# p1-001.net
KiCad netlist of a schematic drawn in EAGLE
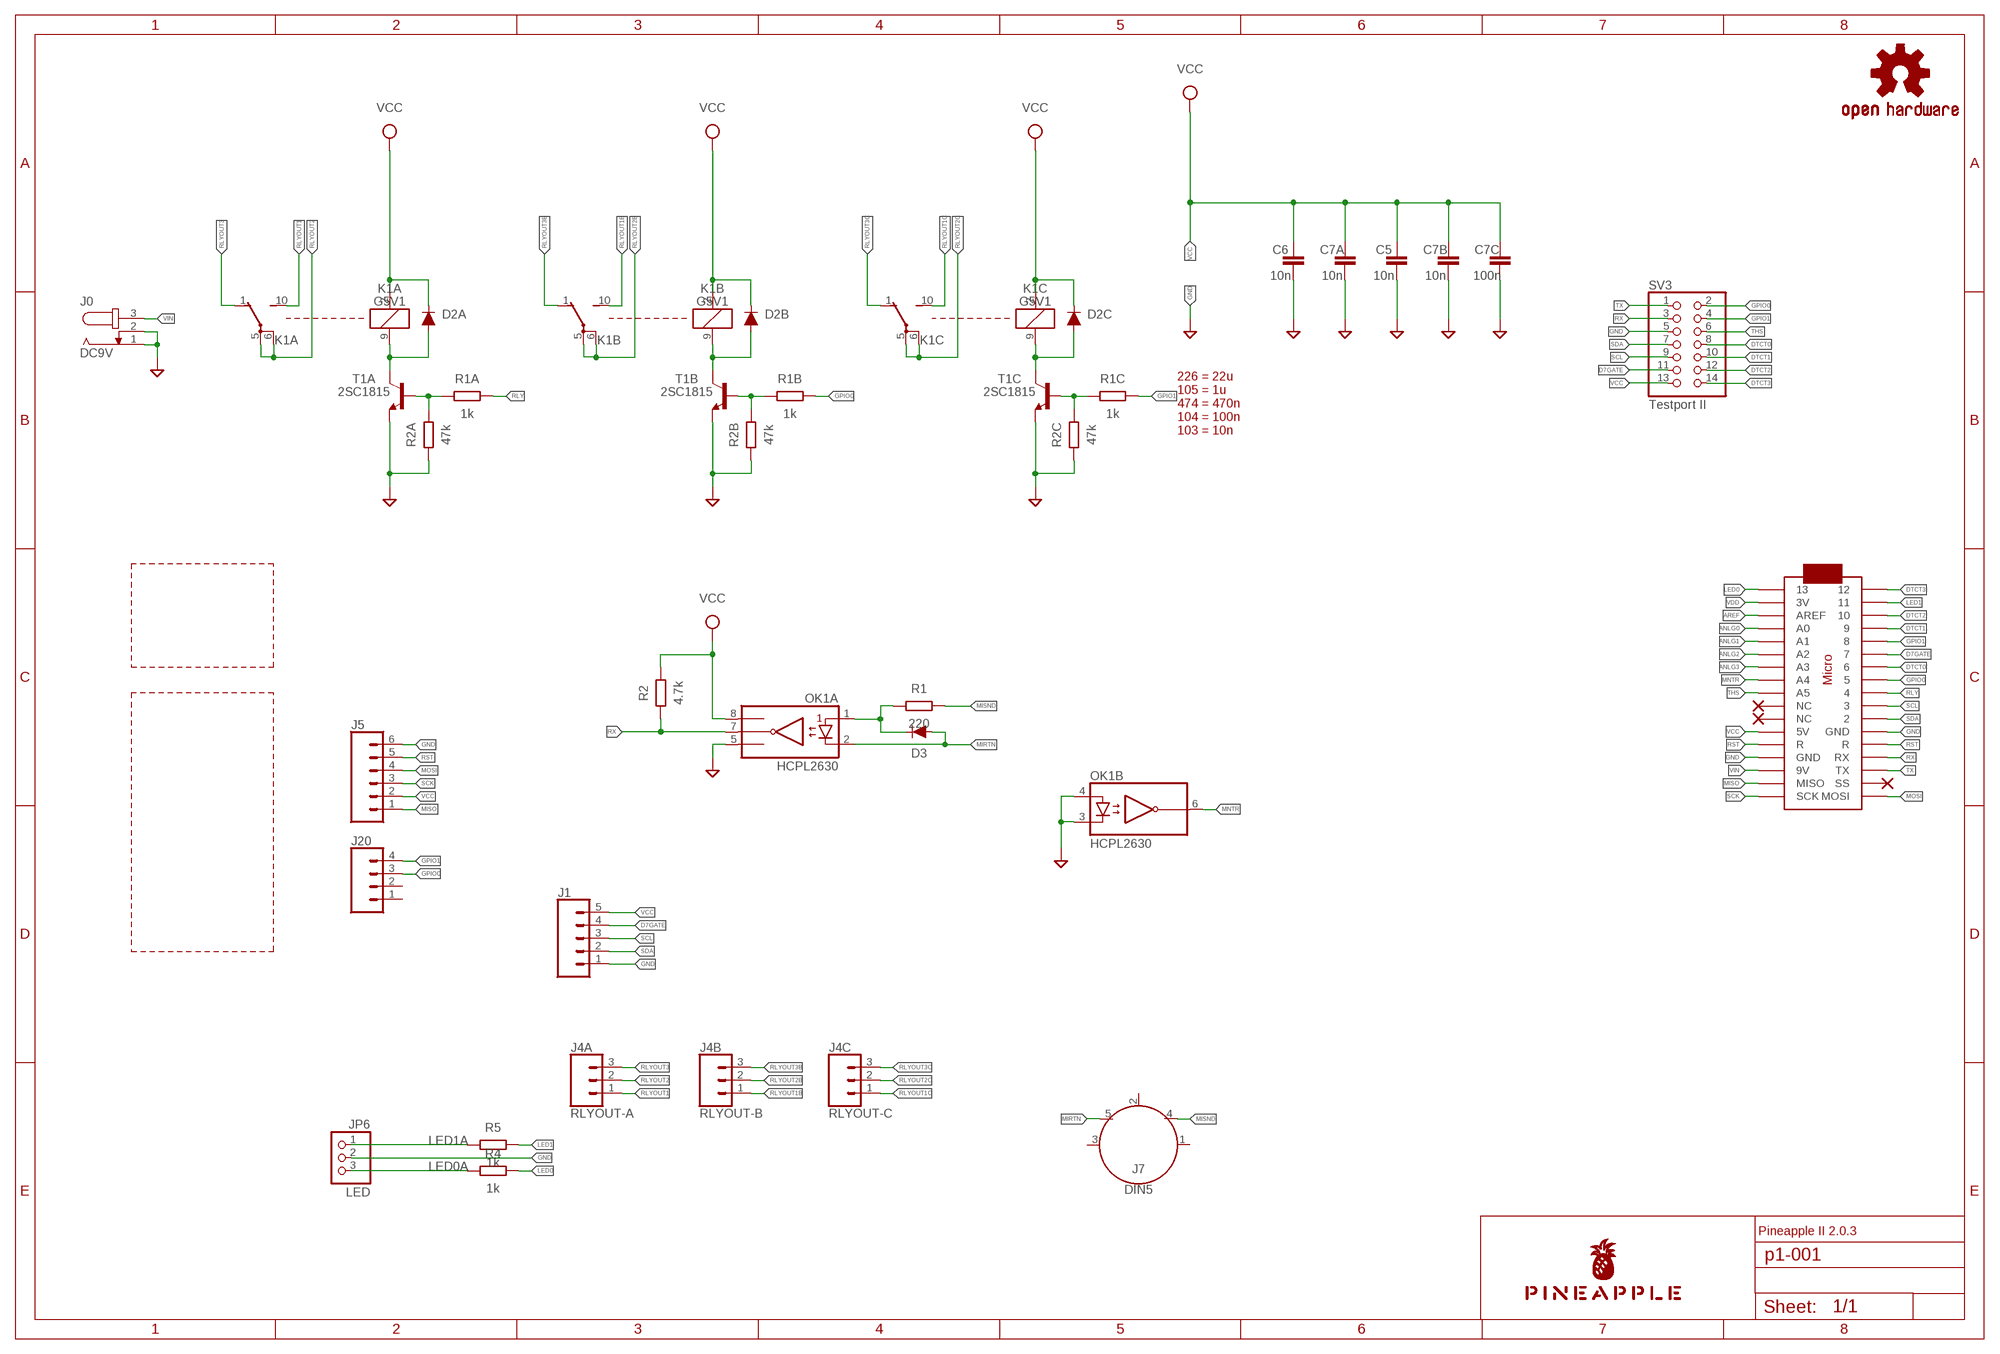
[diagram p0: schematic, sheet 1]

(export (version "E")
  (design (tool "Eeschema 10.0.6"))
  (components
    (comp (ref "C5")
      (value "10n")
      (footprint "eagle-import:C025-024X044")
      (libsource (lib "eagle-import") (part "C-EU025-024X044"))
    )
    (comp (ref "C6")
      (value "10n")
      (footprint "eagle-import:C025-024X044")
      (libsource (lib "eagle-import") (part "C-EU025-024X044"))
    )
    (comp (ref "C7A")
      (value "10n")
      (footprint "eagle-import:C025-024X044")
      (libsource (lib "eagle-import") (part "C-EU025-024X044"))
    )
    (comp (ref "C7B")
      (value "10n")
      (footprint "eagle-import:C025-024X044")
      (libsource (lib "eagle-import") (part "C-EU025-024X044"))
    )
    (comp (ref "C7C")
      (value "100n")
      (footprint "eagle-import:C025-024X044")
      (libsource (lib "eagle-import") (part "C-EU025-024X044"))
    )
    (comp (ref "D2A")
      (value "DIODE-1N4148")
      (footprint "eagle-import:DIODE-1N4148")
      (libsource (lib "eagle-import") (part "DIODE-1N4148"))
    )
    (comp (ref "D2B")
      (value "DIODE-1N4148")
      (footprint "eagle-import:DIODE-1N4148")
      (libsource (lib "eagle-import") (part "DIODE-1N4148"))
    )
    (comp (ref "D2C")
      (value "DIODE-1N4148")
      (footprint "eagle-import:DIODE-1N4148")
      (libsource (lib "eagle-import") (part "DIODE-1N4148"))
    )
    (comp (ref "D3")
      (value "DIODE-1N4148")
      (footprint "eagle-import:DIODE-1N4148")
      (libsource (lib "eagle-import") (part "DIODE-1N4148"))
    )
    (comp (ref "J0")
      (value "DC9V")
      (footprint "eagle-import:SPC4077")
      (libsource (lib "eagle-import") (part "JACK-PLUG0"))
    )
    (comp (ref "J1")
      (value "CONN_05JST")
      (footprint "eagle-import:JST-5-PTH")
      (libsource (lib "eagle-import") (part "CONN_05JST"))
    )
    (comp (ref "J4A")
      (value "RLYOUT-A")
      (footprint "eagle-import:JST-3-PTH")
      (libsource (lib "eagle-import") (part "CONN_03JST-PTH"))
    )
    (comp (ref "J4B")
      (value "RLYOUT-B")
      (footprint "eagle-import:JST-3-PTH")
      (libsource (lib "eagle-import") (part "CONN_03JST-PTH"))
    )
    (comp (ref "J4C")
      (value "RLYOUT-C")
      (footprint "eagle-import:JST-3-PTH")
      (libsource (lib "eagle-import") (part "CONN_03JST-PTH"))
    )
    (comp (ref "J5")
      (value "CONN_061.27MM")
      (footprint "eagle-import:1X06_1.27MM")
      (libsource (lib "eagle-import") (part "CONN_061.27MM"))
    )
    (comp (ref "J7")
      (value "DIN5")
      (footprint "eagle-import:DIN5-RA-PTH")
      (libsource (lib "eagle-import") (part "DIN5"))
    )
    (comp (ref "J20")
      (value "CONN_041.27MM")
      (footprint "eagle-import:1X04_1.27MM")
      (libsource (lib "eagle-import") (part "CONN_041.27MM"))
    )
    (comp (ref "JP6")
      (value "LED")
      (footprint "eagle-import:1X03")
      (libsource (lib "eagle-import") (part "PINHD-1X3"))
    )
    (comp (ref "K1A")
      (value "G5V1")
      (footprint "eagle-import:G5V1")
      (fields (field (name "MPN") "G5V-1-DC24"))
      (libsource (lib "eagle-import") (part "G5V1"))
    )
    (comp (ref "K1B")
      (value "G5V1")
      (footprint "eagle-import:G5V1")
      (fields (field (name "MPN") "G5V-1-DC24"))
      (libsource (lib "eagle-import") (part "G5V1"))
    )
    (comp (ref "K1C")
      (value "G5V1")
      (footprint "eagle-import:G5V1")
      (fields (field (name "MPN") "G5V-1-DC24"))
      (libsource (lib "eagle-import") (part "G5V1"))
    )
    (comp (ref "LOGO1")
      (value "OSHW-LOGOS-COPPER")
      (footprint "eagle-import:OSHW-LOGO-S_COPPER")
      (libsource (lib "eagle-import") (part "OSHW-LOGOS-COPPER"))
    )
    (comp (ref "MC1")
      (value "ARDUINOMICRO")
      (footprint "eagle-import:ARDUINOMICRO")
      (libsource (lib "eagle-import") (part "ARDUINOMICRO"))
    )
    (comp (ref "OK1")
      (value "HCPL2630")
      (footprint "eagle-import:DIL08")
      (fields (field (name "MF") "AGILENT TECHNOLOGIES") (field (name "MPN") "HCPL-2630-000E"))
      (libsource (lib "eagle-import") (part "HCPL2630"))
    )
    (comp (ref "R1")
      (value "220")
      (footprint "eagle-import:0204_5")
      (libsource (lib "eagle-import") (part "R-EU_0204/5"))
    )
    (comp (ref "R1A")
      (value "1k")
      (footprint "eagle-import:0204_5")
      (libsource (lib "eagle-import") (part "R-EU_0204/5"))
    )
    (comp (ref "R1B")
      (value "1k")
      (footprint "eagle-import:0204_5")
      (libsource (lib "eagle-import") (part "R-EU_0204/5"))
    )
    (comp (ref "R1C")
      (value "1k")
      (footprint "eagle-import:0204_5")
      (libsource (lib "eagle-import") (part "R-EU_0204/5"))
    )
    (comp (ref "R2")
      (value "4.7k")
      (footprint "eagle-import:0204_5")
      (libsource (lib "eagle-import") (part "R-EU_0204/5"))
    )
    (comp (ref "R2A")
      (value "47k")
      (footprint "eagle-import:0204_5")
      (libsource (lib "eagle-import") (part "R-EU_0204/5"))
    )
    (comp (ref "R2B")
      (value "47k")
      (footprint "eagle-import:0204_5")
      (libsource (lib "eagle-import") (part "R-EU_0204/5"))
    )
    (comp (ref "R2C")
      (value "47k")
      (footprint "eagle-import:0204_5")
      (libsource (lib "eagle-import") (part "R-EU_0204/5"))
    )
    (comp (ref "R4")
      (value "1k")
      (footprint "eagle-import:0204_5")
      (libsource (lib "eagle-import") (part "R-EU_0204/5"))
    )
    (comp (ref "R5")
      (value "1k")
      (footprint "eagle-import:0204_5")
      (libsource (lib "eagle-import") (part "R-EU_0204/5"))
    )
    (comp (ref "SV3")
      (value "Testport II")
      (footprint "eagle-import:2X07")
      (libsource (lib "eagle-import") (part "PINHD-2X7"))
    )
    (comp (ref "T1A")
      (value "2SC1815")
      (footprint "eagle-import:TO92-ECB")
      (libsource (lib "eagle-import") (part "2SC1815"))
    )
    (comp (ref "T1B")
      (value "2SC1815")
      (footprint "eagle-import:TO92-ECB")
      (libsource (lib "eagle-import") (part "2SC1815"))
    )
    (comp (ref "T1C")
      (value "2SC1815")
      (footprint "eagle-import:TO92-ECB")
      (libsource (lib "eagle-import") (part "2SC1815"))
    )
    (comp (ref "U$1")
      (value "PINEAPPLE450_SILK")
      (footprint "eagle-import:PINEAPPLE450_SILK")
      (libsource (lib "eagle-import") (part "PINEAPPLE450_SILK"))
    )
  )
  (nets
    (net (code "1") (name "/LED0A") (class "Default")
      (node (ref "JP6") (pin "3") (pinfunction "3_3") (pintype "passive"))
      (node (ref "R4") (pin "1") (pinfunction "1_1") (pintype "passive"))
    )
    (net (code "2") (name "/LED1A") (class "Default")
      (node (ref "JP6") (pin "1") (pinfunction "1_1") (pintype "passive"))
      (node (ref "R5") (pin "1") (pinfunction "1_1") (pintype "passive"))
    )
    (net (code "3") (name "ANLG0") (class "Default")
      (node (ref "MC1") (pin "P$31") (pinfunction "A0_P$31") (pintype "bidirectional"))
    )
    (net (code "4") (name "ANLG1") (class "Default")
      (node (ref "MC1") (pin "P$30") (pinfunction "A1_P$30") (pintype "bidirectional"))
    )
    (net (code "5") (name "ANLG2") (class "Default")
      (node (ref "MC1") (pin "P$29") (pinfunction "A2_P$29") (pintype "bidirectional"))
    )
    (net (code "6") (name "ANLG3") (class "Default")
      (node (ref "MC1") (pin "P$28") (pinfunction "A3_P$28") (pintype "bidirectional"))
    )
    (net (code "7") (name "AREF") (class "Default")
      (node (ref "MC1") (pin "P$32") (pinfunction "AREF_P$32") (pintype "bidirectional"))
    )
    (net (code "8") (name "D7GATE") (class "Default")
      (node (ref "J1") (pin "4") (pinfunction "4_4") (pintype "passive"))
      (node (ref "MC1") (pin "P$6") (pinfunction "7_P$6") (pintype "bidirectional"))
      (node (ref "SV3") (pin "11") (pinfunction "11_11") (pintype "passive"))
    )
    (net (code "9") (name "DTCT0") (class "Default")
      (node (ref "MC1") (pin "P$7") (pinfunction "6_P$7") (pintype "bidirectional"))
      (node (ref "SV3") (pin "8") (pinfunction "8_8") (pintype "passive"))
    )
    (net (code "10") (name "DTCT1") (class "Default")
      (node (ref "MC1") (pin "P$4") (pinfunction "9_P$4") (pintype "bidirectional"))
      (node (ref "SV3") (pin "10") (pinfunction "10_10") (pintype "passive"))
    )
    (net (code "11") (name "DTCT2") (class "Default")
      (node (ref "MC1") (pin "P$3") (pinfunction "10_P$3") (pintype "bidirectional"))
      (node (ref "SV3") (pin "12") (pinfunction "12_12") (pintype "passive"))
    )
    (net (code "12") (name "DTCT3") (class "Default")
      (node (ref "MC1") (pin "P$1") (pinfunction "12_P$1") (pintype "bidirectional"))
      (node (ref "SV3") (pin "14") (pinfunction "14_14") (pintype "passive"))
    )
    (net (code "13") (name "GND") (class "Default")
      (node (ref "C5") (pin "2") (pinfunction "2_2") (pintype "passive"))
      (node (ref "C6") (pin "2") (pinfunction "2_2") (pintype "passive"))
      (node (ref "C7A") (pin "2") (pinfunction "2_2") (pintype "passive"))
      (node (ref "C7B") (pin "2") (pinfunction "2_2") (pintype "passive"))
      (node (ref "C7C") (pin "2") (pinfunction "2_2") (pintype "passive"))
      (node (ref "J0") (pin "1") (pinfunction "1_1") (pintype "passive"))
      (node (ref "J0") (pin "2") (pinfunction "2_2") (pintype "passive"))
      (node (ref "J1") (pin "1") (pinfunction "1_1") (pintype "passive"))
      (node (ref "J5") (pin "6") (pinfunction "6_6") (pintype "passive"))
      (node (ref "JP6") (pin "2") (pinfunction "2_2") (pintype "passive"))
      (node (ref "MC1") (pin "P$12") (pinfunction "GND_P$12") (pintype "bidirectional"))
      (node (ref "MC1") (pin "P$21") (pinfunction "GND_P$21") (pintype "bidirectional"))
      (node (ref "OK1") (pin "3") (pinfunction "C2_3") (pintype "passive"))
      (node (ref "OK1") (pin "4") (pinfunction "A2_4") (pintype "passive"))
      (node (ref "OK1") (pin "5") (pinfunction "GND_5") (pintype "passive"))
      (node (ref "R2A") (pin "1") (pinfunction "1_1") (pintype "passive"))
      (node (ref "R2B") (pin "1") (pinfunction "1_1") (pintype "passive"))
      (node (ref "R2C") (pin "1") (pinfunction "1_1") (pintype "passive"))
      (node (ref "SV3") (pin "5") (pinfunction "5_5") (pintype "passive"))
      (node (ref "T1A") (pin "E") (pinfunction "E_E") (pintype "passive"))
      (node (ref "T1B") (pin "E") (pinfunction "E_E") (pintype "passive"))
      (node (ref "T1C") (pin "E") (pinfunction "E_E") (pintype "passive"))
    )
    (net (code "14") (name "GPIO0") (class "Default")
      (node (ref "J20") (pin "3") (pinfunction "3_3") (pintype "passive"))
      (node (ref "MC1") (pin "P$8") (pinfunction "5_P$8") (pintype "bidirectional"))
      (node (ref "R1B") (pin "2") (pinfunction "2_2") (pintype "passive"))
      (node (ref "SV3") (pin "2") (pinfunction "2_2") (pintype "passive"))
    )
    (net (code "15") (name "GPIO1") (class "Default")
      (node (ref "J20") (pin "4") (pinfunction "4_4") (pintype "passive"))
      (node (ref "MC1") (pin "P$5") (pinfunction "8_P$5") (pintype "bidirectional"))
      (node (ref "R1C") (pin "2") (pinfunction "2_2") (pintype "passive"))
      (node (ref "SV3") (pin "4") (pinfunction "4_4") (pintype "passive"))
    )
    (net (code "16") (name "LED0") (class "Default")
      (node (ref "MC1") (pin "P$34") (pinfunction "13_P$34") (pintype "bidirectional"))
      (node (ref "R4") (pin "2") (pinfunction "2_2") (pintype "passive"))
    )
    (net (code "17") (name "LED1") (class "Default")
      (node (ref "MC1") (pin "P$2") (pinfunction "11_P$2") (pintype "bidirectional"))
      (node (ref "R5") (pin "2") (pinfunction "2_2") (pintype "passive"))
    )
    (net (code "18") (name "MIRTN") (class "Default")
      (node (ref "D3") (pin "A") (pinfunction "A_A") (pintype "passive"))
      (node (ref "J7") (pin "5") (pinfunction "5_5") (pintype "bidirectional"))
      (node (ref "OK1") (pin "2") (pinfunction "C1_2") (pintype "passive"))
    )
    (net (code "19") (name "MISND") (class "Default")
      (node (ref "J7") (pin "4") (pinfunction "4_4") (pintype "bidirectional"))
      (node (ref "R1") (pin "2") (pinfunction "2_2") (pintype "passive"))
    )
    (net (code "20") (name "MISO") (class "Default")
      (node (ref "J5") (pin "1") (pinfunction "1_1") (pintype "passive"))
      (node (ref "MC1") (pin "P$19") (pinfunction "MISO_P$19") (pintype "bidirectional"))
    )
    (net (code "21") (name "MNTR") (class "Default")
      (node (ref "MC1") (pin "P$27") (pinfunction "A4_P$27") (pintype "bidirectional"))
      (node (ref "OK1") (pin "6") (pinfunction "VO2_6") (pintype "passive"))
    )
    (net (code "22") (name "MOSI") (class "Default")
      (node (ref "J5") (pin "4") (pinfunction "4_4") (pintype "passive"))
      (node (ref "MC1") (pin "P$17") (pinfunction "MOSI_P$17") (pintype "bidirectional"))
    )
    (net (code "23") (name "Net-(K1AA-2)") (class "Default")
      (node (ref "D2A") (pin "A") (pinfunction "A_A") (pintype "passive"))
      (node (ref "K1A") (pin "9") (pinfunction "2_9") (pintype "passive"))
      (node (ref "T1A") (pin "C") (pinfunction "C_C") (pintype "passive"))
    )
    (net (code "24") (name "Net-(K1BA-2)") (class "Default")
      (node (ref "D2B") (pin "A") (pinfunction "A_A") (pintype "passive"))
      (node (ref "K1B") (pin "9") (pinfunction "2_9") (pintype "passive"))
      (node (ref "T1B") (pin "C") (pinfunction "C_C") (pintype "passive"))
    )
    (net (code "25") (name "Net-(K1CA-2)") (class "Default")
      (node (ref "D2C") (pin "A") (pinfunction "A_A") (pintype "passive"))
      (node (ref "K1C") (pin "9") (pinfunction "2_9") (pintype "passive"))
      (node (ref "T1C") (pin "C") (pinfunction "C_C") (pintype "passive"))
    )
    (net (code "26") (name "Net-(OK1A-A1)") (class "Default")
      (node (ref "D3") (pin "C") (pinfunction "C_C") (pintype "passive"))
      (node (ref "OK1") (pin "1") (pinfunction "A1_1") (pintype "passive"))
      (node (ref "R1") (pin "1") (pinfunction "1_1") (pintype "passive"))
    )
    (net (code "27") (name "Net-(R1A-Pad1)") (class "Default")
      (node (ref "R1A") (pin "1") (pinfunction "1_1") (pintype "passive"))
      (node (ref "R2A") (pin "2") (pinfunction "2_2") (pintype "passive"))
      (node (ref "T1A") (pin "B") (pinfunction "B_B") (pintype "passive"))
    )
    (net (code "28") (name "Net-(R1B-Pad1)") (class "Default")
      (node (ref "R1B") (pin "1") (pinfunction "1_1") (pintype "passive"))
      (node (ref "R2B") (pin "2") (pinfunction "2_2") (pintype "passive"))
      (node (ref "T1B") (pin "B") (pinfunction "B_B") (pintype "passive"))
    )
    (net (code "29") (name "Net-(R1C-Pad1)") (class "Default")
      (node (ref "R1C") (pin "1") (pinfunction "1_1") (pintype "passive"))
      (node (ref "R2C") (pin "2") (pinfunction "2_2") (pintype "passive"))
      (node (ref "T1C") (pin "B") (pinfunction "B_B") (pintype "passive"))
    )
    (net (code "30") (name "RLY") (class "Default")
      (node (ref "MC1") (pin "P$9") (pinfunction "4_P$9") (pintype "bidirectional"))
      (node (ref "R1A") (pin "2") (pinfunction "2_2") (pintype "passive"))
    )
    (net (code "31") (name "RLYOUT1") (class "Default")
      (node (ref "J4A") (pin "1") (pinfunction "1_1") (pintype "passive"))
      (node (ref "K1A") (pin "10") (pinfunction "S_10") (pintype "passive"))
    )
    (net (code "32") (name "RLYOUT1B") (class "Default")
      (node (ref "J4B") (pin "1") (pinfunction "1_1") (pintype "passive"))
      (node (ref "K1B") (pin "10") (pinfunction "S_10") (pintype "passive"))
    )
    (net (code "33") (name "RLYOUT1C") (class "Default")
      (node (ref "J4C") (pin "1") (pinfunction "1_1") (pintype "passive"))
      (node (ref "K1C") (pin "10") (pinfunction "S_10") (pintype "passive"))
    )
    (net (code "34") (name "RLYOUT2") (class "Default")
      (node (ref "J4A") (pin "2") (pinfunction "2_2") (pintype "passive"))
      (node (ref "K1A") (pin "5") (pinfunction "P_5") (pintype "passive"))
      (node (ref "K1A") (pin "6") (pinfunction "P_6") (pintype "passive"))
    )
    (net (code "35") (name "RLYOUT2B") (class "Default")
      (node (ref "J4B") (pin "2") (pinfunction "2_2") (pintype "passive"))
      (node (ref "K1B") (pin "5") (pinfunction "P_5") (pintype "passive"))
      (node (ref "K1B") (pin "6") (pinfunction "P_6") (pintype "passive"))
    )
    (net (code "36") (name "RLYOUT2C") (class "Default")
      (node (ref "J4C") (pin "2") (pinfunction "2_2") (pintype "passive"))
      (node (ref "K1C") (pin "5") (pinfunction "P_5") (pintype "passive"))
      (node (ref "K1C") (pin "6") (pinfunction "P_6") (pintype "passive"))
    )
    (net (code "37") (name "RLYOUT3") (class "Default")
      (node (ref "J4A") (pin "3") (pinfunction "3_3") (pintype "passive"))
      (node (ref "K1A") (pin "1") (pinfunction "O_1") (pintype "passive"))
    )
    (net (code "38") (name "RLYOUT3B") (class "Default")
      (node (ref "J4B") (pin "3") (pinfunction "3_3") (pintype "passive"))
      (node (ref "K1B") (pin "1") (pinfunction "O_1") (pintype "passive"))
    )
    (net (code "39") (name "RLYOUT3C") (class "Default")
      (node (ref "J4C") (pin "3") (pinfunction "3_3") (pintype "passive"))
      (node (ref "K1C") (pin "1") (pinfunction "O_1") (pintype "passive"))
    )
    (net (code "40") (name "RST") (class "Default")
      (node (ref "J5") (pin "5") (pinfunction "5_5") (pintype "passive"))
      (node (ref "MC1") (pin "P$13") (pinfunction "R_P$13") (pintype "bidirectional"))
      (node (ref "MC1") (pin "P$22") (pinfunction "R_P$22") (pintype "bidirectional"))
    )
    (net (code "41") (name "RX") (class "Default")
      (node (ref "MC1") (pin "P$14") (pinfunction "RX_P$14") (pintype "bidirectional"))
      (node (ref "OK1") (pin "7") (pinfunction "VO1_7") (pintype "passive"))
      (node (ref "R2") (pin "1") (pinfunction "1_1") (pintype "passive"))
      (node (ref "SV3") (pin "3") (pinfunction "3_3") (pintype "passive"))
    )
    (net (code "42") (name "SCK") (class "Default")
      (node (ref "J5") (pin "3") (pinfunction "3_3") (pintype "passive"))
      (node (ref "MC1") (pin "P$18") (pinfunction "SCK_P$18") (pintype "bidirectional"))
    )
    (net (code "43") (name "SCL") (class "Default")
      (node (ref "J1") (pin "3") (pinfunction "3_3") (pintype "passive"))
      (node (ref "MC1") (pin "P$10") (pinfunction "3_P$10") (pintype "bidirectional"))
      (node (ref "SV3") (pin "9") (pinfunction "9_9") (pintype "passive"))
    )
    (net (code "44") (name "SDA") (class "Default")
      (node (ref "J1") (pin "2") (pinfunction "2_2") (pintype "passive"))
      (node (ref "MC1") (pin "P$11") (pinfunction "2_P$11") (pintype "bidirectional"))
      (node (ref "SV3") (pin "7") (pinfunction "7_7") (pintype "passive"))
    )
    (net (code "45") (name "THS") (class "Default")
      (node (ref "MC1") (pin "P$26") (pinfunction "A5_P$26") (pintype "bidirectional"))
      (node (ref "SV3") (pin "6") (pinfunction "6_6") (pintype "passive"))
    )
    (net (code "46") (name "TX") (class "Default")
      (node (ref "MC1") (pin "P$15") (pinfunction "TX_P$15") (pintype "bidirectional"))
      (node (ref "SV3") (pin "1") (pinfunction "1_1") (pintype "passive"))
    )
    (net (code "47") (name "VCC") (class "Default")
      (node (ref "C5") (pin "1") (pinfunction "1_1") (pintype "passive"))
      (node (ref "C6") (pin "1") (pinfunction "1_1") (pintype "passive"))
      (node (ref "C7A") (pin "1") (pinfunction "1_1") (pintype "passive"))
      (node (ref "C7B") (pin "1") (pinfunction "1_1") (pintype "passive"))
      (node (ref "C7C") (pin "1") (pinfunction "1_1") (pintype "passive"))
      (node (ref "D2A") (pin "C") (pinfunction "C_C") (pintype "passive"))
      (node (ref "D2B") (pin "C") (pinfunction "C_C") (pintype "passive"))
      (node (ref "D2C") (pin "C") (pinfunction "C_C") (pintype "passive"))
      (node (ref "J1") (pin "5") (pinfunction "5_5") (pintype "passive"))
      (node (ref "J5") (pin "2") (pinfunction "2_2") (pintype "passive"))
      (node (ref "K1A") (pin "2") (pinfunction "1_2") (pintype "passive"))
      (node (ref "K1B") (pin "2") (pinfunction "1_2") (pintype "passive"))
      (node (ref "K1C") (pin "2") (pinfunction "1_2") (pintype "passive"))
      (node (ref "MC1") (pin "P$23") (pinfunction "5V_P$23") (pintype "bidirectional"))
      (node (ref "OK1") (pin "8") (pinfunction "VCC_8") (pintype "passive"))
      (node (ref "R2") (pin "2") (pinfunction "2_2") (pintype "passive"))
      (node (ref "SV3") (pin "13") (pinfunction "13_13") (pintype "passive"))
    )
    (net (code "48") (name "VDD") (class "Default")
      (node (ref "MC1") (pin "P$33") (pinfunction "3V_P$33") (pintype "bidirectional"))
    )
    (net (code "49") (name "VIN") (class "Default")
      (node (ref "J0") (pin "3") (pinfunction "3_3") (pintype "passive"))
      (node (ref "MC1") (pin "P$20") (pinfunction "9V_P$20") (pintype "bidirectional"))
    )
    (net (code "50") (name "unconnected-(J7-Pad1)") (class "Default")
      (node (ref "J7") (pin "1") (pinfunction "1_1") (pintype "bidirectional"))
    )
    (net (code "51") (name "unconnected-(J7-Pad2)") (class "Default")
      (node (ref "J7") (pin "2") (pinfunction "2_2") (pintype "bidirectional"))
    )
    (net (code "52") (name "unconnected-(J7-Pad3)") (class "Default")
      (node (ref "J7") (pin "3") (pinfunction "3_3") (pintype "bidirectional"))
    )
    (net (code "53") (name "unconnected-(J20-Pad1)") (class "Default")
      (node (ref "J20") (pin "1") (pinfunction "1_1") (pintype "passive"))
    )
    (net (code "54") (name "unconnected-(J20-Pad2)") (class "Default")
      (node (ref "J20") (pin "2") (pinfunction "2_2") (pintype "passive"))
    )
    (net (code "55") (name "unconnected-(MC1-NC-PadP$24)") (class "Default")
      (node (ref "MC1") (pin "P$24") (pinfunction "NC_P$24") (pintype "bidirectional"))
    )
    (net (code "56") (name "unconnected-(MC1-NC-PadP$25)") (class "Default")
      (node (ref "MC1") (pin "P$25") (pinfunction "NC_P$25") (pintype "bidirectional"))
    )
    (net (code "57") (name "unconnected-(MC1-SS-PadP$16)") (class "Default")
      (node (ref "MC1") (pin "P$16") (pinfunction "SS_P$16") (pintype "bidirectional"))
    )
  )
)
